# INA219_CH5.net
KiCad netlist of a schematic drawn in Altium Designer
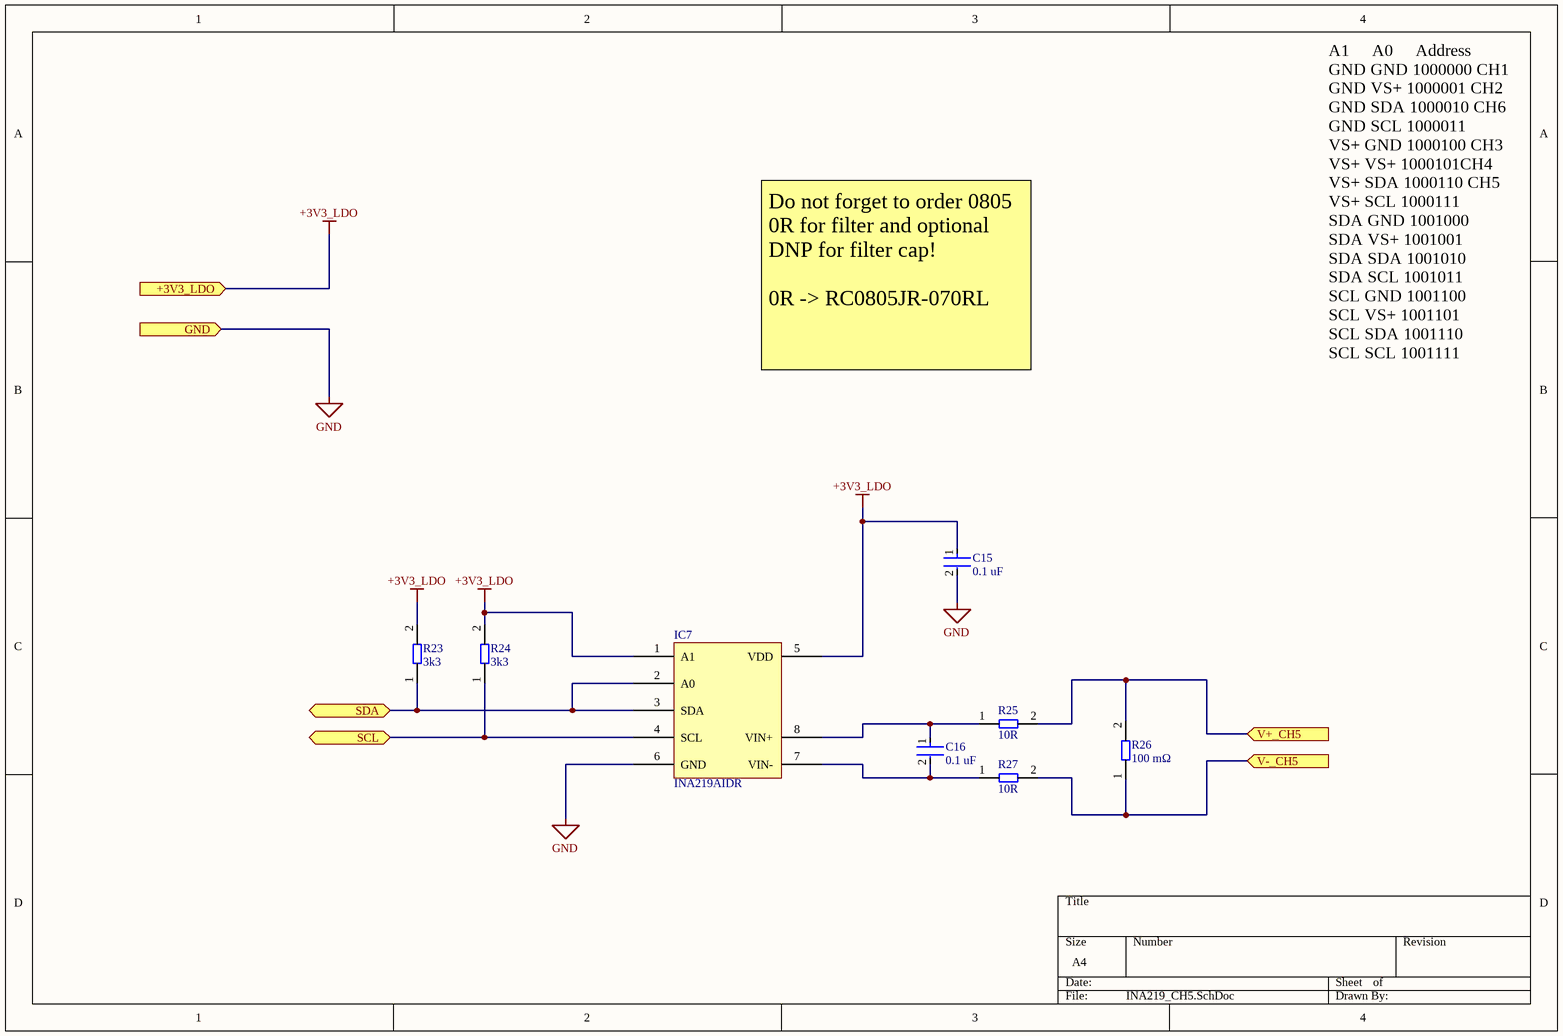
[diagram p0: INA219_CH5.SchDoc]

(export (version "E")
  (design (tool "Eeschema 10.0.6"))
  (components
    (comp (ref "C15")
      (value "0.1 uF")
      (footprint "FP-C0805C-DN-MFG")
      (description "C0805 0.10 μF X7R 30ppm/°C 20.00% 50 V C0805C104M5RAC")
      (fields
        (field (name "MANUFACTURER PART NUMBER") "C0805C104M5RAC")
        (field (name "MANUFACTURER") "KEMET")
      )
      (libsource (lib "Altium Content Vault") (part "b4654b650e69147ec39a6b967a45e02"))
    )
    (comp (ref "C16")
      (value "0.1 uF")
      (footprint "FP-C0805C-DN-MFG")
      (description "C0805 0.10 μF X7R 30ppm/°C 20.00% 50 V C0805C104M5RAC")
      (fields
        (field (name "MANUFACTURER PART NUMBER") "C0805C104M5RAC")
        (field (name "MANUFACTURER") "KEMET")
      )
      (libsource (lib "Altium Content Vault") (part "b4654b650e69147ec39a6b967a45e02"))
    )
    (comp (ref "IC7")
      (value "INA219AIDR")
      (footprint "INA219AIDR")
      (description "Current & Power Monitors & Regulators Zero-Drift,Bi-Dir Crnt/Pwr Monitor")
      (libsource (lib "Callisto Control Board") (part "INA219AIDR"))
    )
    (comp (ref "R23")
      (value "3k3")
      (footprint "0805 Resistor - IPC A")
      (description "Thick Film Resistors - SMD 3.3 kOhms 125 mW 0805 1%\r\nRE0805FRE073K3L")
      (libsource (lib "Callisto Control Board") (part "RE0805FRE073K3L"))
    )
    (comp (ref "R24")
      (value "3k3")
      (footprint "0805 Resistor - IPC A")
      (description "Thick Film Resistors - SMD 3.3 kOhms 125 mW 0805 1%\r\nRE0805FRE073K3L")
      (libsource (lib "Callisto Control Board") (part "RE0805FRE073K3L"))
    )
    (comp (ref "R25")
      (value "10R")
      (footprint "0805 Resistor - IPC A")
      (description "Thick Film Resistors - SMD 10 Ohms 125 mW 0805 1%\r\nRC0805FR-0710RL")
      (libsource (lib "Callisto Control Board") (part "RC0805FR-0710RL"))
    )
    (comp (ref "R26")
      (value "100 mΩ")
      (footprint "PE2512FKM070R1L")
      (description "Current Sense Resistors - SMD 100 mOhms 1 Watt 1 % 75 ppm/C AEC-Q200\r\nPE2512FKM070R1L")
      (libsource (lib "Callisto Control Board") (part "PE2512FKM070R1L"))
    )
    (comp (ref "R27")
      (value "10R")
      (footprint "0805 Resistor - IPC A")
      (description "Thick Film Resistors - SMD 10 Ohms 125 mW 0805 1%\r\nRC0805FR-0710RL")
      (libsource (lib "Callisto Control Board") (part "RC0805FR-0710RL"))
    )
  )
  (nets
    (net (code "1") (name "+3V3_LDO") (class "Default")
      (node (ref "C15") (pin "1") (pinfunction "1_1") (pintype "passive"))
      (node (ref "IC7") (pin "1") (pinfunction "A1_1") (pintype "passive"))
      (node (ref "IC7") (pin "5") (pinfunction "VDD_5") (pintype "passive"))
      (node (ref "R23") (pin "2") (pintype "passive"))
      (node (ref "R24") (pin "2") (pintype "passive"))
    )
    (net (code "2") (name "/SCL") (class "Default")
      (node (ref "IC7") (pin "4") (pinfunction "SCL_4") (pintype "passive"))
      (node (ref "R24") (pin "1") (pintype "passive"))
    )
    (net (code "3") (name "/SDA") (class "Default")
      (node (ref "IC7") (pin "2") (pinfunction "A0_2") (pintype "passive"))
      (node (ref "IC7") (pin "3") (pinfunction "SDA_3") (pintype "passive"))
      (node (ref "R23") (pin "1") (pintype "passive"))
    )
    (net (code "4") (name "/V+_CH5") (class "Default")
      (node (ref "R25") (pin "2") (pintype "passive"))
      (node (ref "R26") (pin "2") (pintype "passive"))
    )
    (net (code "5") (name "/V-_CH5") (class "Default")
      (node (ref "R26") (pin "1") (pintype "passive"))
      (node (ref "R27") (pin "2") (pintype "passive"))
    )
    (net (code "6") (name "GND") (class "Default")
      (node (ref "C15") (pin "2") (pinfunction "2_2") (pintype "passive"))
      (node (ref "IC7") (pin "6") (pinfunction "GND_6") (pintype "passive"))
    )
    (net (code "7") (name "Net-(IC7-VIN+)") (class "Default")
      (node (ref "C16") (pin "1") (pinfunction "1_1") (pintype "passive"))
      (node (ref "IC7") (pin "8") (pinfunction "VIN+_8") (pintype "passive"))
      (node (ref "R25") (pin "1") (pintype "passive"))
    )
    (net (code "8") (name "Net-(IC7-VIN-)") (class "Default")
      (node (ref "C16") (pin "2") (pinfunction "2_2") (pintype "passive"))
      (node (ref "IC7") (pin "7") (pinfunction "VIN-_7") (pintype "passive"))
      (node (ref "R27") (pin "1") (pintype "passive"))
    )
  )
)
